# sensor_sunstone.net
KiCad netlist of a schematic drawn in EAGLE
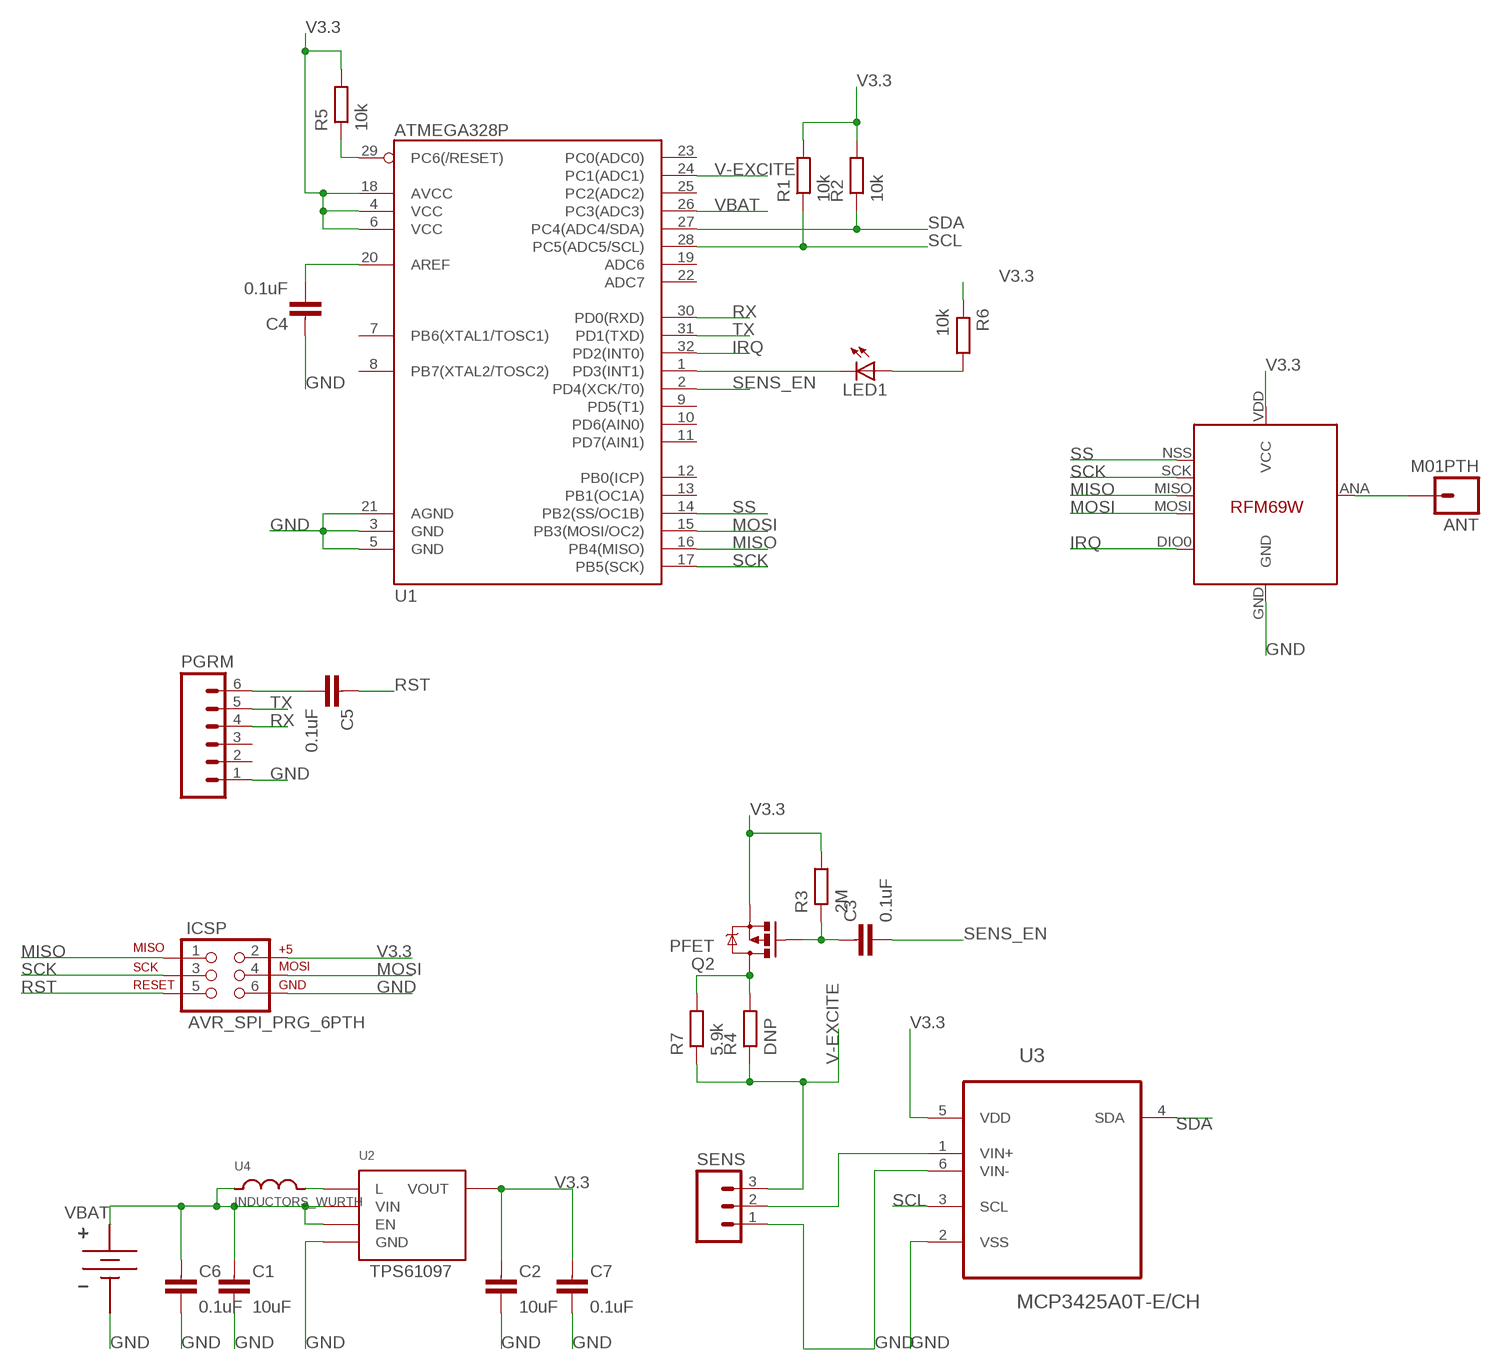
[diagram p0: schematic, sheet 1]

(export (version "E")
  (design (tool "Eeschema 10.0.6"))
  (components
    (comp (ref "ANT")
      (value "M01PTH")
      (footprint "eagle-import:1X01")
      (libsource (lib "eagle-import") (part "M01PTH"))
    )
    (comp (ref "C1")
      (value "10uF")
      (footprint "eagle-import:C0805-N")
      (libsource (lib "eagle-import") (part "CAPACITOR0805-N"))
    )
    (comp (ref "C2")
      (value "10uF")
      (footprint "eagle-import:C0805-N")
      (libsource (lib "eagle-import") (part "CAPACITOR0805-N"))
    )
    (comp (ref "C3")
      (value "0.1uF")
      (footprint "eagle-import:C0603-N")
      (libsource (lib "eagle-import") (part "CAPACITOR0603-N"))
    )
    (comp (ref "C4")
      (value "0.1uF")
      (footprint "eagle-import:C0603-N")
      (libsource (lib "eagle-import") (part "CAPACITOR0603-N"))
    )
    (comp (ref "C5")
      (value "0.1uF")
      (footprint "eagle-import:C0603-N")
      (libsource (lib "eagle-import") (part "CAPACITOR0603-N"))
    )
    (comp (ref "C6")
      (value "0.1uF")
      (footprint "eagle-import:C0603-N")
      (libsource (lib "eagle-import") (part "CAPACITOR0603-N"))
    )
    (comp (ref "C7")
      (value "0.1uF")
      (footprint "eagle-import:C0603-N")
      (libsource (lib "eagle-import") (part "CAPACITOR0603-N"))
    )
    (comp (ref "ICSP")
      (value "AVR_SPI_PRG_6PTH")
      (footprint "eagle-import:2X3")
      (libsource (lib "eagle-import") (part "AVR_SPI_PRG_6PTH"))
    )
    (comp (ref "LED1")
      (value "LED0603")
      (footprint "eagle-import:LED-0603")
      (libsource (lib "eagle-import") (part "LED0603"))
    )
    (comp (ref "PGRM")
      (value "M06LONGPADS")
      (footprint "eagle-import:1X06_LONGPADS")
      (libsource (lib "eagle-import") (part "M06LONGPADS"))
    )
    (comp (ref "Q2")
      (value "PFET")
      (footprint "eagle-import:SOT23-3")
      (libsource (lib "eagle-import") (part "MOSFET-PCHANNELIRLML2244"))
    )
    (comp (ref "R1")
      (value "10k")
      (footprint "eagle-import:R0603-N")
      (libsource (lib "eagle-import") (part "RESISTOR0603-N"))
    )
    (comp (ref "R2")
      (value "10k")
      (footprint "eagle-import:R0603-N")
      (libsource (lib "eagle-import") (part "RESISTOR0603-N"))
    )
    (comp (ref "R3")
      (value "2M")
      (footprint "eagle-import:R0603-N")
      (libsource (lib "eagle-import") (part "RESISTOR0603-N"))
    )
    (comp (ref "R4")
      (value "DNP")
      (footprint "eagle-import:R0603-N")
      (libsource (lib "eagle-import") (part "RESISTOR0603-N"))
    )
    (comp (ref "R5")
      (value "10k")
      (footprint "eagle-import:R0603-N")
      (libsource (lib "eagle-import") (part "RESISTOR0603-N"))
    )
    (comp (ref "R6")
      (value "10k")
      (footprint "eagle-import:R0603-N")
      (libsource (lib "eagle-import") (part "RESISTOR0603-N"))
    )
    (comp (ref "R7")
      (value "5.9k")
      (footprint "eagle-import:R0603-N")
      (libsource (lib "eagle-import") (part "RESISTOR0603-N"))
    )
    (comp (ref "SENS")
      (value "M03PTH")
      (footprint "eagle-import:1X03")
      (libsource (lib "eagle-import") (part "M03PTH"))
    )
    (comp (ref "U$1")
      (value "KEYSTONEAAHOLDER_2CELL")
      (footprint "eagle-import:KEYSTONEAAHOLDER_2CELL")
      (libsource (lib "eagle-import") (part "KEYSTONEAAHOLDER_2CELL"))
    )
    (comp (ref "U$5")
      (value "RFM69")
      (footprint "eagle-import:RFM69W-MINPADS")
      (libsource (lib "eagle-import") (part "RFM69"))
    )
    (comp (ref "U1")
      (value "ATMEGA328P")
      (footprint "eagle-import:TQFP32-08")
      (libsource (lib "eagle-import") (part "ATMEGA328_SMT"))
    )
    (comp (ref "U2")
      (value "TPS61097-33")
      (footprint "eagle-import:SOT23-5")
      (libsource (lib "eagle-import") (part "TPS61097-33"))
    )
    (comp (ref "U3")
      (value "MCP3425A0T-E/CH")
      (footprint "eagle-import:SOT95P270X145-6N")
      (libsource (lib "eagle-import") (part "MCP3425A0T-E/CH"))
    )
    (comp (ref "U4")
      (value "INDUCTORS_WURTH")
      (footprint "eagle-import:WURTH_10UH_650MA")
      (libsource (lib "eagle-import") (part "INDUCTORS_WURTH"))
    )
  )
  (nets
    (net (code "1") (name "/GND") (class "Default")
      (node (ref "C1") (pin "2") (pinfunction "2_2") (pintype "passive"))
      (node (ref "C2") (pin "2") (pinfunction "2_2") (pintype "passive"))
      (node (ref "C4") (pin "1") (pinfunction "1_1") (pintype "passive"))
      (node (ref "C6") (pin "2") (pinfunction "2_2") (pintype "passive"))
      (node (ref "C7") (pin "2") (pinfunction "2_2") (pintype "passive"))
      (node (ref "ICSP") (pin "6") (pinfunction "6_6") (pintype "passive"))
      (node (ref "PGRM") (pin "1") (pinfunction "1_1") (pintype "passive"))
      (node (ref "SENS") (pin "1") (pinfunction "1_1") (pintype "passive"))
      (node (ref "U$1") (pin "P$2") (pinfunction "GND_P$2") (pintype "bidirectional"))
      (node (ref "U$5") (pin "GND") (pinfunction "GND_GND") (pintype "power_in"))
      (node (ref "U1") (pin "21") (pinfunction "AGND_21") (pintype "bidirectional"))
      (node (ref "U1") (pin "3") (pinfunction "GND_3") (pintype "bidirectional"))
      (node (ref "U1") (pin "5") (pinfunction "GND_5") (pintype "bidirectional"))
      (node (ref "U2") (pin "P$2") (pinfunction "GND_P$2") (pintype "power_in"))
      (node (ref "U3") (pin "2") (pinfunction "VSS_2") (pintype "passive"))
      (node (ref "U3") (pin "6") (pinfunction "VIN-_6") (pintype "input"))
    )
    (net (code "2") (name "/IRQ") (class "Default")
      (node (ref "U$5") (pin "DIO0") (pinfunction "DIO0_DIO0") (pintype "open_collector"))
      (node (ref "U1") (pin "32") (pinfunction "PD2(INT0)_32") (pintype "bidirectional"))
    )
    (net (code "3") (name "/MISO") (class "Default")
      (node (ref "ICSP") (pin "1") (pinfunction "1_1") (pintype "passive"))
      (node (ref "U$5") (pin "MISO") (pinfunction "MISO_MISO") (pintype "input"))
      (node (ref "U1") (pin "16") (pinfunction "PB4(MISO)_16") (pintype "bidirectional"))
    )
    (net (code "4") (name "/MOSI") (class "Default")
      (node (ref "ICSP") (pin "4") (pinfunction "4_4") (pintype "passive"))
      (node (ref "U$5") (pin "MOSI") (pinfunction "MOSI_MOSI") (pintype "output"))
      (node (ref "U1") (pin "15") (pinfunction "PB3(MOSI/OC2)_15") (pintype "bidirectional"))
    )
    (net (code "5") (name "/RST") (class "Default")
      (node (ref "C5") (pin "1") (pinfunction "1_1") (pintype "passive"))
      (node (ref "ICSP") (pin "5") (pinfunction "5_5") (pintype "passive"))
      (node (ref "R5") (pin "1") (pinfunction "P$1_1") (pintype "passive"))
      (node (ref "U1") (pin "29") (pinfunction "PC6(/RESET)_29") (pintype "bidirectional"))
    )
    (net (code "6") (name "/RX") (class "Default")
      (node (ref "PGRM") (pin "4") (pinfunction "4_4") (pintype "passive"))
      (node (ref "U1") (pin "30") (pinfunction "PD0(RXD)_30") (pintype "bidirectional"))
    )
    (net (code "7") (name "/SCK") (class "Default")
      (node (ref "ICSP") (pin "3") (pinfunction "3_3") (pintype "passive"))
      (node (ref "U$5") (pin "SCK") (pinfunction "SCK_SCK") (pintype "input"))
      (node (ref "U1") (pin "17") (pinfunction "PB5(SCK)_17") (pintype "bidirectional"))
    )
    (net (code "8") (name "/SCL") (class "Default")
      (node (ref "R1") (pin "1") (pinfunction "P$1_1") (pintype "passive"))
      (node (ref "U1") (pin "28") (pinfunction "PC5(ADC5/SCL)_28") (pintype "bidirectional"))
      (node (ref "U3") (pin "3") (pinfunction "SCL_3") (pintype "input"))
    )
    (net (code "9") (name "/SDA") (class "Default")
      (node (ref "R2") (pin "1") (pinfunction "P$1_1") (pintype "passive"))
      (node (ref "U1") (pin "27") (pinfunction "PC4(ADC4/SDA)_27") (pintype "bidirectional"))
      (node (ref "U3") (pin "4") (pinfunction "SDA_4") (pintype "bidirectional"))
    )
    (net (code "10") (name "/SENS_EN") (class "Default")
      (node (ref "C3") (pin "2") (pinfunction "2_2") (pintype "passive"))
      (node (ref "U1") (pin "2") (pinfunction "PD4(XCK/T0)_2") (pintype "bidirectional"))
    )
    (net (code "11") (name "/SS") (class "Default")
      (node (ref "U$5") (pin "NSS") (pinfunction "SEL_NSS") (pintype "input"))
      (node (ref "U1") (pin "14") (pinfunction "PB2(SS/OC1B)_14") (pintype "bidirectional"))
    )
    (net (code "12") (name "/TX") (class "Default")
      (node (ref "PGRM") (pin "5") (pinfunction "5_5") (pintype "passive"))
      (node (ref "U1") (pin "31") (pinfunction "PD1(TXD)_31") (pintype "bidirectional"))
    )
    (net (code "13") (name "/V-EXCITE") (class "Default")
      (node (ref "R4") (pin "1") (pinfunction "P$1_1") (pintype "passive"))
      (node (ref "R7") (pin "1") (pinfunction "P$1_1") (pintype "passive"))
      (node (ref "SENS") (pin "3") (pinfunction "3_3") (pintype "passive"))
      (node (ref "U1") (pin "24") (pinfunction "PC1(ADC1)_24") (pintype "bidirectional"))
    )
    (net (code "14") (name "/V3.3") (class "Default")
      (node (ref "C2") (pin "1") (pinfunction "1_1") (pintype "passive"))
      (node (ref "C7") (pin "1") (pinfunction "1_1") (pintype "passive"))
      (node (ref "ICSP") (pin "2") (pinfunction "2_2") (pintype "passive"))
      (node (ref "Q2") (pin "2") (pinfunction "S_2") (pintype "passive"))
      (node (ref "R1") (pin "2") (pinfunction "P$2_2") (pintype "passive"))
      (node (ref "R2") (pin "2") (pinfunction "P$2_2") (pintype "passive"))
      (node (ref "R3") (pin "2") (pinfunction "P$2_2") (pintype "passive"))
      (node (ref "R5") (pin "2") (pinfunction "P$2_2") (pintype "passive"))
      (node (ref "R6") (pin "1") (pinfunction "P$1_1") (pintype "passive"))
      (node (ref "U$5") (pin "VDD") (pinfunction "VCC_VDD") (pintype "power_in"))
      (node (ref "U1") (pin "18") (pinfunction "AVCC_18") (pintype "bidirectional"))
      (node (ref "U1") (pin "4") (pinfunction "VCC_4") (pintype "bidirectional"))
      (node (ref "U1") (pin "6") (pinfunction "VCC_6") (pintype "bidirectional"))
      (node (ref "U2") (pin "P$4") (pinfunction "VOUT_P$4") (pintype "power_in"))
      (node (ref "U3") (pin "5") (pinfunction "VDD_5") (pintype "power_in"))
    )
    (net (code "15") (name "/VBAT") (class "Default")
      (node (ref "C1") (pin "1") (pinfunction "1_1") (pintype "passive"))
      (node (ref "C6") (pin "1") (pinfunction "1_1") (pintype "passive"))
      (node (ref "U$1") (pin "P$1") (pinfunction "VBAT_P$1") (pintype "bidirectional"))
      (node (ref "U1") (pin "26") (pinfunction "PC3(ADC3)_26") (pintype "bidirectional"))
      (node (ref "U2") (pin "P$1") (pinfunction "VIN_P$1") (pintype "power_in"))
      (node (ref "U2") (pin "P$3") (pinfunction "EN_P$3") (pintype "bidirectional"))
      (node (ref "U4") (pin "P$2") (pinfunction "P$2_P$2") (pintype "passive"))
    )
    (net (code "16") (name "Net-(C5-Pad2)") (class "Default")
      (node (ref "C5") (pin "2") (pinfunction "2_2") (pintype "passive"))
      (node (ref "PGRM") (pin "6") (pinfunction "6_6") (pintype "passive"))
    )
    (net (code "17") (name "Net-(Q2-D)") (class "Default")
      (node (ref "Q2") (pin "3") (pinfunction "D_3") (pintype "passive"))
      (node (ref "R4") (pin "2") (pinfunction "P$2_2") (pintype "passive"))
      (node (ref "R7") (pin "2") (pinfunction "P$2_2") (pintype "passive"))
    )
    (net (code "18") (name "Net-(Q2-G)") (class "Default")
      (node (ref "C3") (pin "1") (pinfunction "1_1") (pintype "passive"))
      (node (ref "Q2") (pin "1") (pinfunction "G_1") (pintype "passive"))
      (node (ref "R3") (pin "1") (pinfunction "P$1_1") (pintype "passive"))
    )
    (net (code "19") (name "Net-(R6-P$2)") (class "Default")
      (node (ref "LED1") (pin "A") (pinfunction "A_A") (pintype "passive"))
      (node (ref "R6") (pin "2") (pinfunction "P$2_2") (pintype "passive"))
    )
    (net (code "20") (name "Net-(U$5-ANT)") (class "Default")
      (node (ref "ANT") (pin "1") (pinfunction "1_1") (pintype "passive"))
      (node (ref "U$5") (pin "ANA") (pinfunction "ANT_ANA") (pintype "passive"))
    )
    (net (code "21") (name "Net-(U1-AREF)") (class "Default")
      (node (ref "C4") (pin "2") (pinfunction "2_2") (pintype "passive"))
      (node (ref "U1") (pin "20") (pinfunction "AREF_20") (pintype "bidirectional"))
    )
    (net (code "22") (name "Net-(U1-PD3(INT1))") (class "Default")
      (node (ref "LED1") (pin "C") (pinfunction "C_C") (pintype "passive"))
      (node (ref "U1") (pin "1") (pinfunction "PD3(INT1)_1") (pintype "bidirectional"))
    )
    (net (code "23") (name "Net-(U2-L)") (class "Default")
      (node (ref "U2") (pin "P$5") (pinfunction "L_P$5") (pintype "bidirectional"))
      (node (ref "U4") (pin "P$1") (pinfunction "P$1_P$1") (pintype "passive"))
    )
    (net (code "24") (name "Net-(U3-VIN+)") (class "Default")
      (node (ref "SENS") (pin "2") (pinfunction "2_2") (pintype "passive"))
      (node (ref "U3") (pin "1") (pinfunction "VIN+_1") (pintype "input"))
    )
    (net (code "25") (name "unconnected-(PGRM-Pad2)") (class "Default")
      (node (ref "PGRM") (pin "2") (pinfunction "2_2") (pintype "passive"))
    )
    (net (code "26") (name "unconnected-(PGRM-Pad3)") (class "Default")
      (node (ref "PGRM") (pin "3") (pinfunction "3_3") (pintype "passive"))
    )
    (net (code "27") (name "unconnected-(U1-ADC6-Pad19)") (class "Default")
      (node (ref "U1") (pin "19") (pinfunction "ADC6_19") (pintype "bidirectional"))
    )
    (net (code "28") (name "unconnected-(U1-ADC7-Pad22)") (class "Default")
      (node (ref "U1") (pin "22") (pinfunction "ADC7_22") (pintype "bidirectional"))
    )
    (net (code "29") (name "unconnected-(U1-PB0(ICP)-Pad12)") (class "Default")
      (node (ref "U1") (pin "12") (pinfunction "PB0(ICP)_12") (pintype "bidirectional"))
    )
    (net (code "30") (name "unconnected-(U1-PB1(OC1A)-Pad13)") (class "Default")
      (node (ref "U1") (pin "13") (pinfunction "PB1(OC1A)_13") (pintype "bidirectional"))
    )
    (net (code "31") (name "unconnected-(U1-PB6(XTAL1{slash}TOSC1)-Pad7)") (class "Default")
      (node (ref "U1") (pin "7") (pinfunction "PB6(XTAL1/TOSC1)_7") (pintype "bidirectional"))
    )
    (net (code "32") (name "unconnected-(U1-PB7(XTAL2{slash}TOSC2)-Pad8)") (class "Default")
      (node (ref "U1") (pin "8") (pinfunction "PB7(XTAL2/TOSC2)_8") (pintype "bidirectional"))
    )
    (net (code "33") (name "unconnected-(U1-PC0(ADC0)-Pad23)") (class "Default")
      (node (ref "U1") (pin "23") (pinfunction "PC0(ADC0)_23") (pintype "bidirectional"))
    )
    (net (code "34") (name "unconnected-(U1-PC2(ADC2)-Pad25)") (class "Default")
      (node (ref "U1") (pin "25") (pinfunction "PC2(ADC2)_25") (pintype "bidirectional"))
    )
    (net (code "35") (name "unconnected-(U1-PD5(T1)-Pad9)") (class "Default")
      (node (ref "U1") (pin "9") (pinfunction "PD5(T1)_9") (pintype "bidirectional"))
    )
    (net (code "36") (name "unconnected-(U1-PD6(AIN0)-Pad10)") (class "Default")
      (node (ref "U1") (pin "10") (pinfunction "PD6(AIN0)_10") (pintype "bidirectional"))
    )
    (net (code "37") (name "unconnected-(U1-PD7(AIN1)-Pad11)") (class "Default")
      (node (ref "U1") (pin "11") (pinfunction "PD7(AIN1)_11") (pintype "bidirectional"))
    )
  )
)
